# P00160_5_28_P.net
KiCad netlist of a schematic drawn in Altium Designer
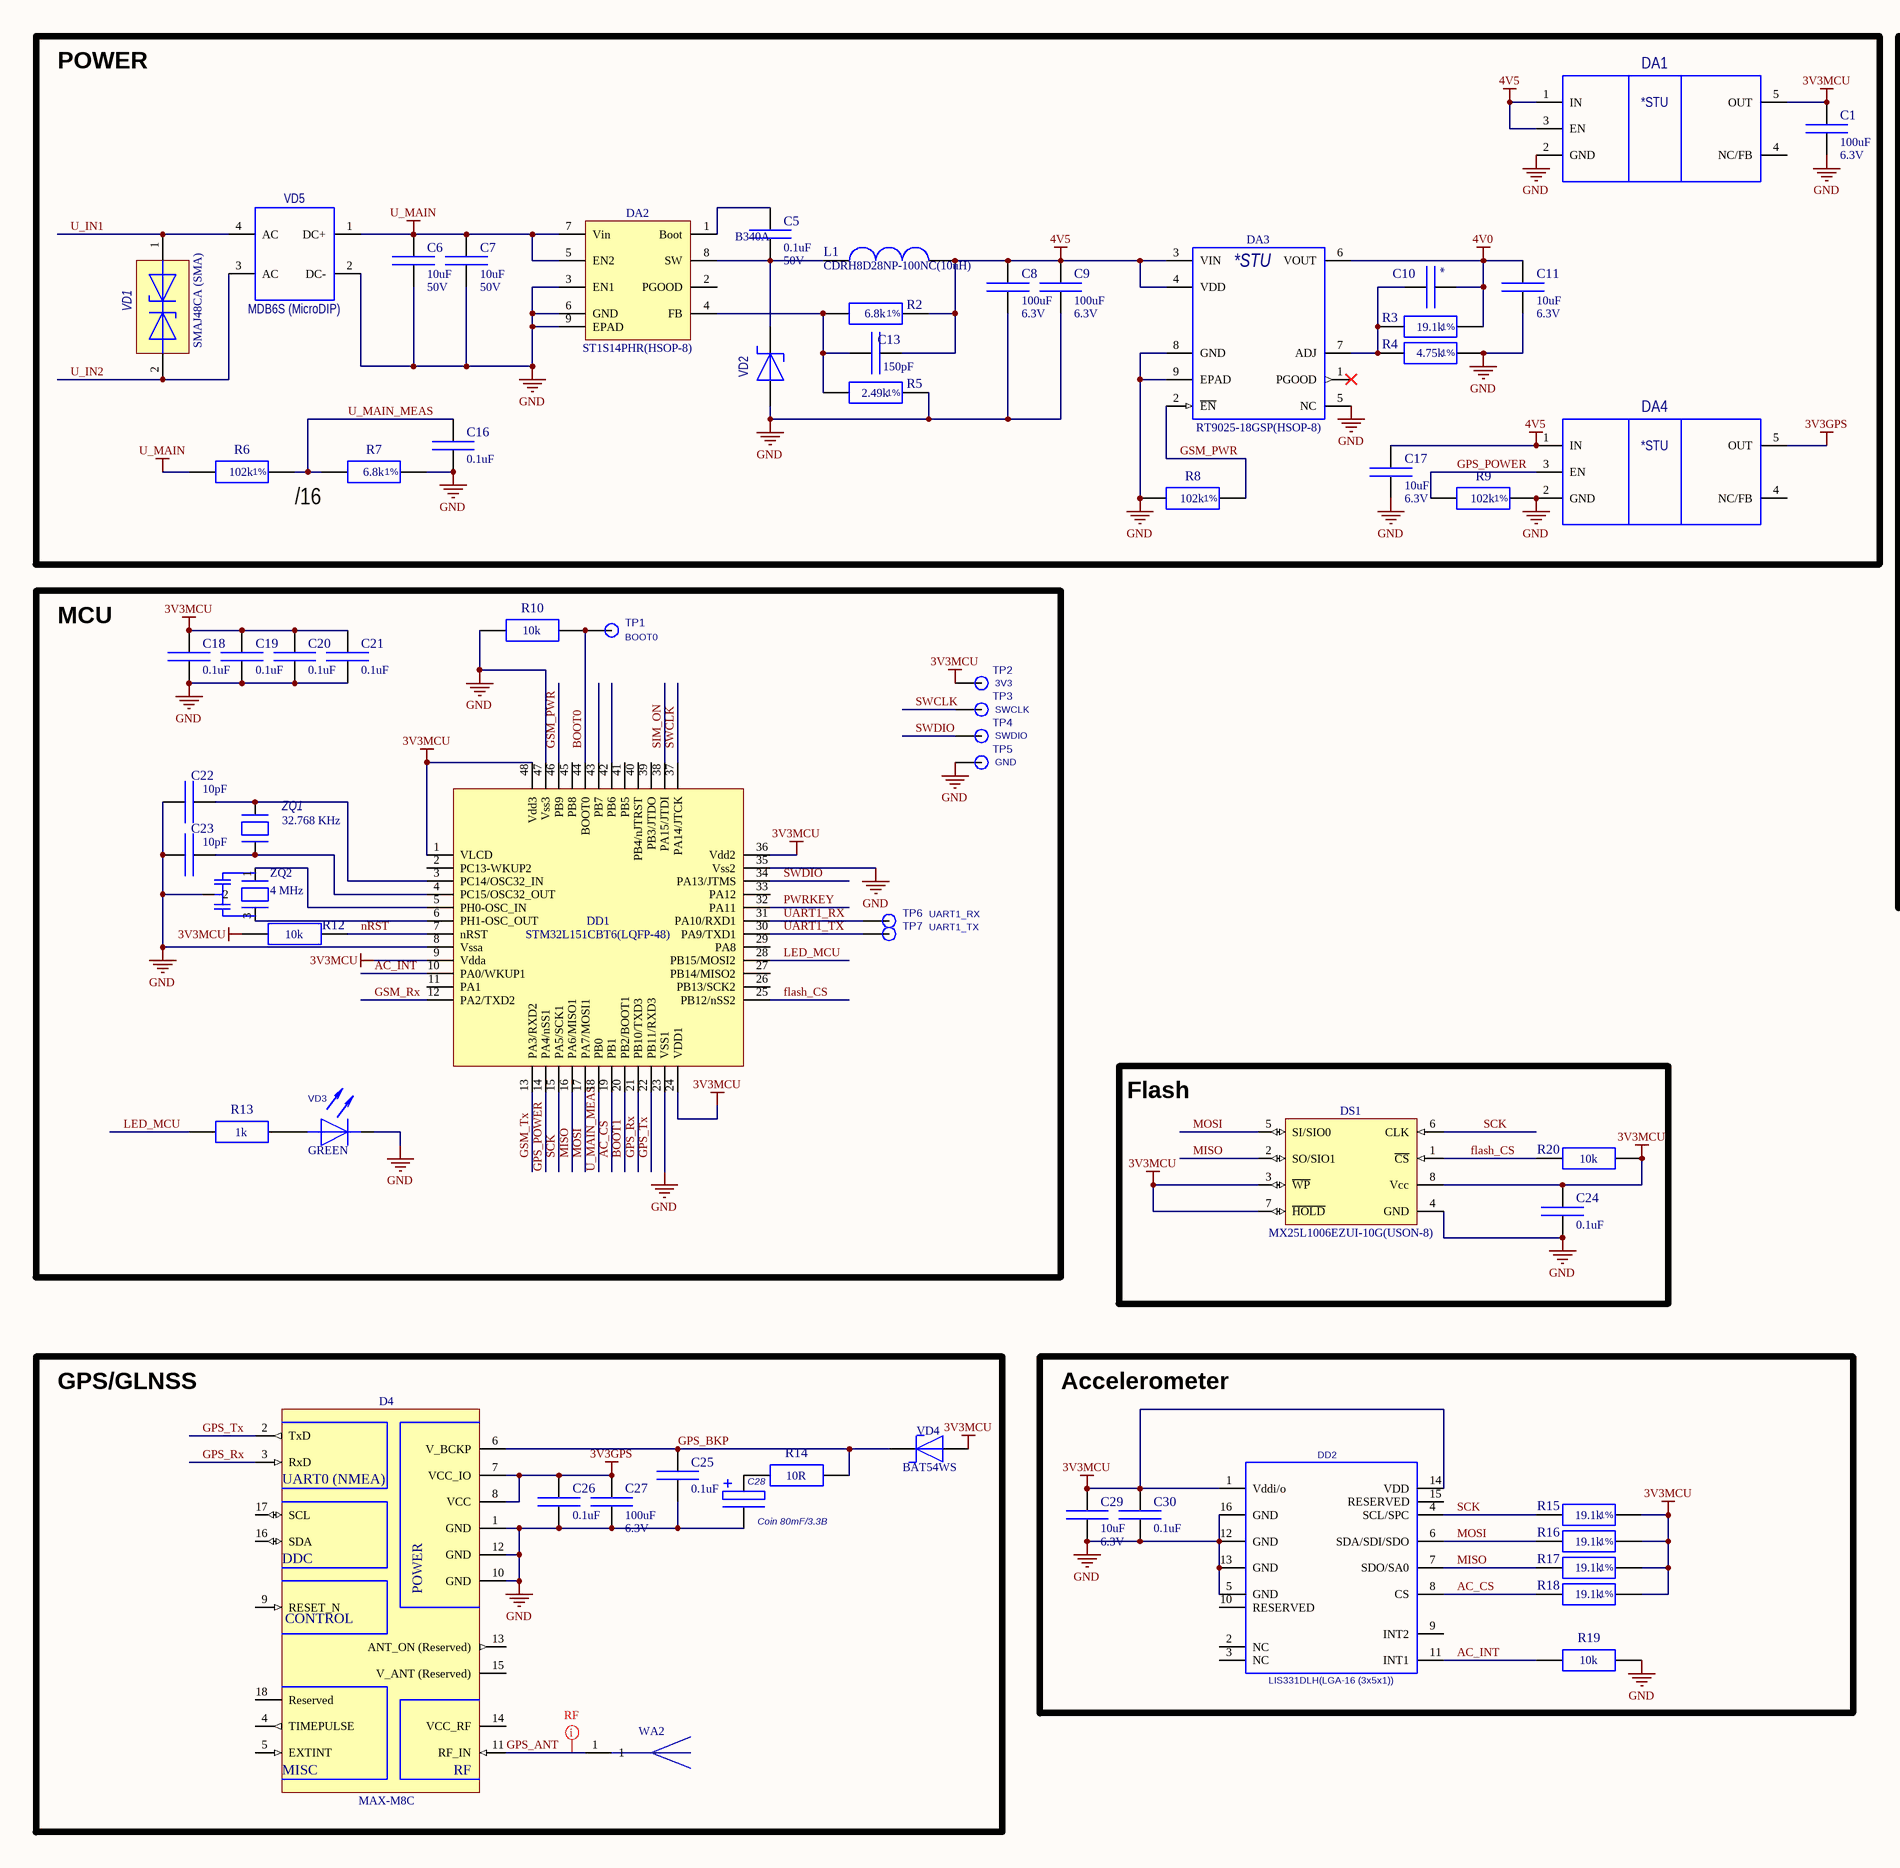
[diagram p0: P00160.5.28_P.SchDoc, left]
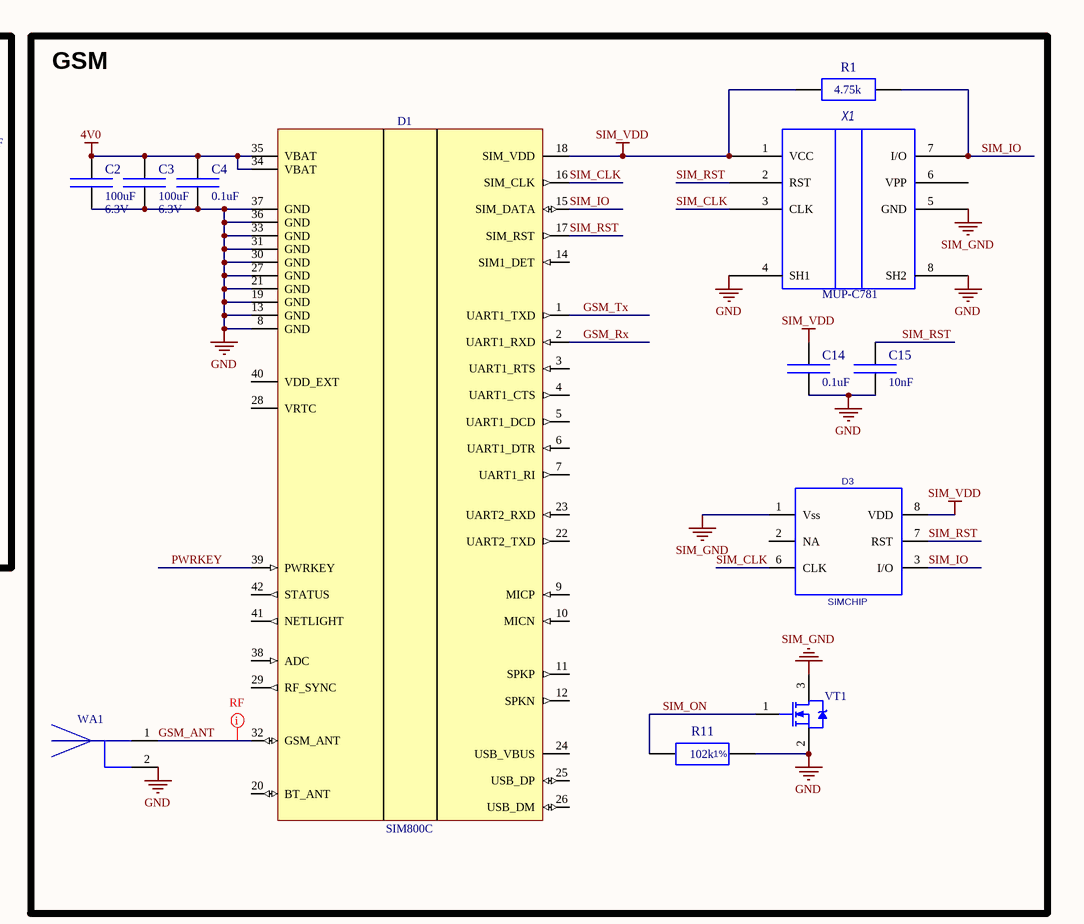
[diagram p1: P00160.5.28_P.SchDoc, right]

(export (version "E")
  (design (tool "Eeschema 10.0.6"))
  (components
    (comp (ref "C1")
      (value "100uF")
      (footprint "CAPC3216X135(1206)")
      (description "C1206")
      (fields (field (name "PARVOLTAGE") "6.3V") (field (name "Comment") "чип 1206 100uF/6.3V, "))
      (libsource (lib "pass_smd") (part "C1206"))
    )
    (comp (ref "C2")
      (value "100uF")
      (footprint "CAPC3216X135(1206)")
      (description "C1206")
      (fields (field (name "PARVOLTAGE") "6.3V") (field (name "Comment") "чип 1206 100uF/6.3V, "))
      (libsource (lib "pass_smd") (part "C1206"))
    )
    (comp (ref "C3")
      (value "100uF")
      (footprint "CAPC3216X135(1206)")
      (description "C1206")
      (fields (field (name "PARVOLTAGE") "6.3V") (field (name "Comment") "чип 1206 100uF/6.3V, "))
      (libsource (lib "pass_smd") (part "C1206"))
    )
    (comp (ref "C4")
      (value "0.1uF")
      (footprint "CAPC1005X50(0402)")
      (description "C0402")
      (fields (field (name "Comment") "чип 0402 0.1uF/10V, "))
      (libsource (lib "pass_smd") (part "C0402"))
    )
    (comp (ref "C5")
      (value "0.1uF")
      (footprint "CAPC1608X50(0603)")
      (description "C0603")
      (fields (field (name "PARVOLTAGE") "50V") (field (name "Comment") "чип 0603 0.1uF/50V, "))
      (libsource (lib "pass_smd") (part "C0603"))
    )
    (comp (ref "C6")
      (value "10uF")
      (footprint "CAPC3216X135(1206)")
      (description "C1206")
      (fields
        (field (name "CMPPARTNUM") "CL31A106KBHNNNE")
        (field (name "PARVOLTAGE") "50V")
        (field (name "Comment") "чип 1206 10uF/50V, ")
      )
      (libsource (lib "pass_smd") (part "C1206"))
    )
    (comp (ref "C7")
      (value "10uF")
      (footprint "CAPC3216X135(1206)")
      (description "C1206")
      (fields
        (field (name "CMPPARTNUM") "CL31A106KBHNNNE")
        (field (name "PARVOLTAGE") "50V")
        (field (name "Comment") "чип 1206 10uF/50V, ")
      )
      (libsource (lib "pass_smd") (part "C1206"))
    )
    (comp (ref "C8")
      (value "100uF")
      (footprint "CAPC3216X135(1206)")
      (description "C1206")
      (fields (field (name "PARVOLTAGE") "6.3V") (field (name "Comment") "чип 1206 100uF/6.3V, "))
      (libsource (lib "pass_smd") (part "C1206"))
    )
    (comp (ref "C9")
      (value "100uF")
      (footprint "CAPC3216X135(1206)")
      (description "C1206")
      (fields (field (name "PARVOLTAGE") "6.3V") (field (name "Comment") "чип 1206 100uF/6.3V, "))
      (libsource (lib "pass_smd") (part "C1206"))
    )
    (comp (ref "C10")
      (value "чип 0402 */,")
      (footprint "CAPC1005X50(0402)")
      (description "C0402")
      (fields (field (name "ALTIUM_VALUE") "*"))
      (libsource (lib "pass_smd") (part "C0402"))
    )
    (comp (ref "C11")
      (value "10uF")
      (footprint "CAPC1608X50(0603)")
      (description "C0603")
      (fields (field (name "PARVOLTAGE") "6.3V") (field (name "Comment") "чип 0603 10uF/6.3V, "))
      (libsource (lib "pass_smd") (part "C0603"))
    )
    (comp (ref "C13")
      (value "150pF")
      (footprint "CAPC1005X50(0402)")
      (description "C0402")
      (fields (field (name "Comment") "чип 0402 150pF/50V, "))
      (libsource (lib "pass_smd") (part "C0402"))
    )
    (comp (ref "C14")
      (value "0.1uF")
      (footprint "CAPC1005X50(0402)")
      (description "C0402")
      (fields (field (name "Comment") "чип 0402 0.1uF/10V, "))
      (libsource (lib "pass_smd") (part "C0402"))
    )
    (comp (ref "C15")
      (value "10nF")
      (footprint "CAPC1005X50(0402)")
      (description "C0402")
      (fields (field (name "Comment") "чип 0402 10nF/10V, "))
      (libsource (lib "pass_smd") (part "C0402"))
    )
    (comp (ref "C16")
      (value "0.1uF")
      (footprint "CAPC1005X50(0402)")
      (description "C0402")
      (fields (field (name "Comment") "чип 0402 0.1uF/10V, "))
      (libsource (lib "pass_smd") (part "C0402"))
    )
    (comp (ref "C17")
      (value "10uF")
      (footprint "CAPC1608X50(0603)")
      (description "C0603")
      (fields (field (name "PARVOLTAGE") "6.3V") (field (name "Comment") "чип 0603 10uF/6.3V, "))
      (libsource (lib "pass_smd") (part "C0603"))
    )
    (comp (ref "C18")
      (value "0.1uF")
      (footprint "CAPC1005X50(0402)")
      (description "C0402")
      (fields (field (name "Comment") "чип 0402 0.1uF/10V, "))
      (libsource (lib "pass_smd") (part "C0402"))
    )
    (comp (ref "C19")
      (value "0.1uF")
      (footprint "CAPC1005X50(0402)")
      (description "C0402")
      (fields (field (name "Comment") "чип 0402 0.1uF/10V, "))
      (libsource (lib "pass_smd") (part "C0402"))
    )
    (comp (ref "C20")
      (value "0.1uF")
      (footprint "CAPC1005X50(0402)")
      (description "C0402")
      (fields (field (name "Comment") "чип 0402 0.1uF/10V, "))
      (libsource (lib "pass_smd") (part "C0402"))
    )
    (comp (ref "C21")
      (value "0.1uF")
      (footprint "CAPC1005X50(0402)")
      (description "C0402")
      (fields (field (name "Comment") "чип 0402 0.1uF/10V, "))
      (libsource (lib "pass_smd") (part "C0402"))
    )
    (comp (ref "C22")
      (value "10pF")
      (footprint "CAPC1005X50(0402)")
      (description "C0402")
      (fields (field (name "Comment") "чип 0402 10pF/10V, "))
      (libsource (lib "pass_smd") (part "C0402"))
    )
    (comp (ref "C23")
      (value "10pF")
      (footprint "CAPC1005X50(0402)")
      (description "C0402")
      (fields (field (name "Comment") "чип 0402 10pF/10V, "))
      (libsource (lib "pass_smd") (part "C0402"))
    )
    (comp (ref "C24")
      (value "0.1uF")
      (footprint "CAPC1005X50(0402)")
      (description "C0402")
      (fields (field (name "Comment") "чип 0402 0.1uF/10V, "))
      (libsource (lib "pass_smd") (part "C0402"))
    )
    (comp (ref "C25")
      (value "0.1uF")
      (footprint "CAPC1005X50(0402)")
      (description "C0402")
      (fields (field (name "Comment") "чип 0402 0.1uF/10V, "))
      (libsource (lib "pass_smd") (part "C0402"))
    )
    (comp (ref "C26")
      (value "0.1uF")
      (footprint "CAPC1005X50(0402)")
      (description "C0402")
      (fields (field (name "Comment") "чип 0402 0.1uF/10V, "))
      (libsource (lib "pass_smd") (part "C0402"))
    )
    (comp (ref "C27")
      (value "100uF")
      (footprint "CAPC3216X135(1206)")
      (description "C1206")
      (fields (field (name "PARVOLTAGE") "6.3V") (field (name "Comment") "чип 1206 100uF/6.3V, "))
      (libsource (lib "pass_smd") (part "C1206"))
    )
    (comp (ref "C28")
      (value "Coin 80mF/3.3В")
      (footprint "XH414HG-IV01E")
      (description "ELECTRIC DOUBLE LAYER CAPACITORS")
      (fields (field (name "CMPPARTNUM") "XH414HG-IV01E"))
      (libsource (lib "MyLib") (part "XH414HG-IV01E"))
    )
    (comp (ref "C29")
      (value "10uF")
      (footprint "CAPC1608X50(0603)")
      (description "C0603")
      (fields (field (name "PARVOLTAGE") "6.3V") (field (name "Comment") "чип 0603 10uF/6.3V, "))
      (libsource (lib "pass_smd") (part "C0603"))
    )
    (comp (ref "C30")
      (value "0.1uF")
      (footprint "CAPC1005X50(0402)")
      (description "C0402")
      (fields (field (name "Comment") "чип 0402 0.1uF/10V, "))
      (libsource (lib "pass_smd") (part "C0402"))
    )
    (comp (ref "D1")
      (value "SIM800C")
      (footprint "SIMCOM800C")
      (libsource (lib "gsm_modules") (part "SIM800C"))
    )
    (comp (ref "D3")
      (value "SIMCHIP")
      (footprint "VQFN127P600-8N")
      (fields (field (name "CMPPARTNUM") "MFF2 SIM"))
      (libsource (lib "Misc") (part "SIMCHIP"))
    )
    (comp (ref "D4") (value "MAX-M8C") (footprint "MAX-7") (libsource (lib "gps_modules") (part "MAX-7")))
    (comp (ref "DA1")
      (value "TPS76333DBV(SOT23-5)")
      (footprint "SOT95P285X130-5N(SOT23-5)")
      (description "TPS76333DBV")
      (libsource (lib "TI") (part "TPS76333DBV"))
    )
    (comp (ref "DA2")
      (value "ST1S14PHR(HSOP-8)")
      (footprint "HSOP127P-8N")
      (fields (field (name "CMPPARTNUM") "ST1S14PHR"))
      (libsource (lib "ST") (part "ST1S14"))
    )
    (comp (ref "DA3")
      (value "RT9025-18GSP(HSOP-8)")
      (footprint "HSOP127P-8N")
      (description "2A, Ultra Low Dropout LDO")
      (fields (field (name "CMPPARTNUM") "RT9025-18GSP"))
      (libsource (lib "Richtek") (part "RT9025"))
    )
    (comp (ref "DA4")
      (value "TPS76333DBV(SOT23-5)")
      (footprint "SOT95P285X130-5N(SOT23-5)")
      (description "TPS76333DBV")
      (libsource (lib "TI") (part "TPS76333DBV"))
    )
    (comp (ref "DD1")
      (value "STM32L151CBT6(LQFP-48)")
      (footprint "TSQFP50P900X900X160-48N")
      (description "STM32L151CxU6")
      (fields (field (name "CMPPARTNUM") "STM32L151CBT6"))
      (libsource (lib "ST") (part "STM32L151CxU6"))
    )
    (comp (ref "DD2")
      (value "LIS331DLH(LGA-16 (3x5x1))")
      (footprint "LGA16S50P3X5_300X300X100")
      (description "MEMS digital output motion sensor  ultra low-power high performance 3-axes “nano” accelerometer")
      (fields (field (name "CMPPARTNUM") "LIS331DLH"))
      (libsource (lib "ST") (part "LIS331DLH"))
    )
    (comp (ref "DS1")
      (value "MX25L1006EZUI-10G(USON-8)")
      (footprint "SON50P300X60_HS-9N")
      (description "1M-BIT [x 1/x 2] CMOS SERIAL FLASH")
      (fields (field (name "CMPPARTNUM") "MX25L1006EZUI-10G"))
      (libsource (lib "ROMs") (part "MX25L1006E"))
    )
    (comp (ref "L1")
      (value "CDRH8D28NP-100NC(10uH)")
      (footprint "CDRH8D28NP")
      (description "CDRH8D28NP")
      (fields (field (name "CMPPARTNUM") "CDRH8D28NP-100NC"))
      (libsource (lib "pass_smd") (part "CDRH8D28NP"))
    )
    (comp (ref "R1")
      (value "4.75k")
      (footprint "RESC1005X35(0402)")
      (description "R0402")
      (fields (field (name "TOLERANCE") "1%") (field (name "Comment") "чип 0402 4.75k 1%"))
      (libsource (lib "pass_smd") (part "R0402"))
    )
    (comp (ref "R2")
      (value "6.8k")
      (footprint "RESC1005X35(0402)")
      (description "R0402")
      (fields (field (name "TOLERANCE") "1%") (field (name "Comment") "чип 0402 6.8k 1%"))
      (libsource (lib "pass_smd") (part "R0402"))
    )
    (comp (ref "R3")
      (value "19.1k")
      (footprint "RESC1005X35(0402)")
      (description "R0402")
      (fields (field (name "TOLERANCE") "1%") (field (name "Comment") "чип 0402 19.1k 1%"))
      (libsource (lib "pass_smd") (part "R0402"))
    )
    (comp (ref "R4")
      (value "4.75k")
      (footprint "RESC1005X35(0402)")
      (description "R0402")
      (fields (field (name "TOLERANCE") "1%") (field (name "Comment") "чип 0402 4.75k 1%"))
      (libsource (lib "pass_smd") (part "R0402"))
    )
    (comp (ref "R5")
      (value "2.49k")
      (footprint "RESC1005X35(0402)")
      (description "R0402")
      (fields (field (name "TOLERANCE") "1%") (field (name "Comment") "чип 0402 2.49k 1%"))
      (libsource (lib "pass_smd") (part "R0402"))
    )
    (comp (ref "R6")
      (value "102k")
      (footprint "RESC1005X35(0402)")
      (description "R0402")
      (fields (field (name "TOLERANCE") "1%") (field (name "Comment") "чип 0402 102k 1%"))
      (libsource (lib "pass_smd") (part "R0402"))
    )
    (comp (ref "R7")
      (value "6.8k")
      (footprint "RESC1005X35(0402)")
      (description "R0402")
      (fields (field (name "TOLERANCE") "1%") (field (name "Comment") "чип 0402 6.8k 1%"))
      (libsource (lib "pass_smd") (part "R0402"))
    )
    (comp (ref "R8")
      (value "102k")
      (footprint "RESC1005X35(0402)")
      (description "R0402")
      (fields (field (name "TOLERANCE") "1%") (field (name "Comment") "чип 0402 102k 1%"))
      (libsource (lib "pass_smd") (part "R0402"))
    )
    (comp (ref "R9")
      (value "102k")
      (footprint "RESC1005X35(0402)")
      (description "R0402")
      (fields (field (name "TOLERANCE") "1%") (field (name "Comment") "чип 0402 102k 1%"))
      (libsource (lib "pass_smd") (part "R0402"))
    )
    (comp (ref "R10")
      (value "10k")
      (footprint "RESC1005X35(0402)")
      (description "R0402")
      (fields (field (name "TOLERANCE") "5%") (field (name "Comment") "чип 0402 10k 5%"))
      (libsource (lib "pass_smd") (part "R0402"))
    )
    (comp (ref "R11")
      (value "102k")
      (footprint "RESC1005X35(0402)")
      (description "R0402")
      (fields (field (name "TOLERANCE") "1%") (field (name "Comment") "чип 0402 102k 1%"))
      (libsource (lib "pass_smd") (part "R0402"))
    )
    (comp (ref "R12")
      (value "10k")
      (footprint "RESC1005X35(0402)")
      (description "R0402")
      (fields (field (name "TOLERANCE") "5%") (field (name "Comment") "чип 0402 10k 5%"))
      (libsource (lib "pass_smd") (part "R0402"))
    )
    (comp (ref "R13")
      (value "1k")
      (footprint "RESC1005X35(0402)")
      (description "R0402")
      (fields (field (name "TOLERANCE") "5%") (field (name "Comment") "чип 0402 1k 5%"))
      (libsource (lib "pass_smd") (part "R0402"))
    )
    (comp (ref "R14")
      (value "10R")
      (footprint "RESC1005X35(0402)")
      (description "R0402")
      (fields (field (name "TOLERANCE") "5%") (field (name "Comment") "чип 0402 10R 5%"))
      (libsource (lib "pass_smd") (part "R0402"))
    )
    (comp (ref "R15")
      (value "19.1k")
      (footprint "RESC1005X35(0402)")
      (description "R0402")
      (fields (field (name "TOLERANCE") "1%") (field (name "Comment") "чип 0402 19.1k 1%"))
      (libsource (lib "pass_smd") (part "R0402"))
    )
    (comp (ref "R16")
      (value "19.1k")
      (footprint "RESC1005X35(0402)")
      (description "R0402")
      (fields (field (name "TOLERANCE") "1%") (field (name "Comment") "чип 0402 19.1k 1%"))
      (libsource (lib "pass_smd") (part "R0402"))
    )
    (comp (ref "R17")
      (value "19.1k")
      (footprint "RESC1005X35(0402)")
      (description "R0402")
      (fields (field (name "TOLERANCE") "1%") (field (name "Comment") "чип 0402 19.1k 1%"))
      (libsource (lib "pass_smd") (part "R0402"))
    )
    (comp (ref "R18")
      (value "19.1k")
      (footprint "RESC1005X35(0402)")
      (description "R0402")
      (fields (field (name "TOLERANCE") "1%") (field (name "Comment") "чип 0402 19.1k 1%"))
      (libsource (lib "pass_smd") (part "R0402"))
    )
    (comp (ref "R19")
      (value "10k")
      (footprint "RESC1005X35(0402)")
      (description "R0402")
      (fields (field (name "TOLERANCE") "5%") (field (name "Comment") "чип 0402 10k 5%"))
      (libsource (lib "pass_smd") (part "R0402"))
    )
    (comp (ref "R20")
      (value "10k")
      (footprint "RESC1005X35(0402)")
      (description "R0402")
      (fields (field (name "TOLERANCE") "5%") (field (name "Comment") "чип 0402 10k 5%"))
      (libsource (lib "pass_smd") (part "R0402"))
    )
    (comp (ref "TP1")
      (value "BOOT0")
      (footprint "TEST_POINT")
      (description "TEST_POINT")
      (libsource (lib "connectors") (part "TEST_POINT"))
    )
    (comp (ref "TP2")
      (value "3V3")
      (footprint "TEST_POINT")
      (description "TEST_POINT")
      (libsource (lib "connectors") (part "TEST_POINT"))
    )
    (comp (ref "TP3")
      (value "SWCLK")
      (footprint "TEST_POINT")
      (description "TEST_POINT")
      (libsource (lib "connectors") (part "TEST_POINT"))
    )
    (comp (ref "TP4")
      (value "SWDIO")
      (footprint "TEST_POINT")
      (description "TEST_POINT")
      (libsource (lib "connectors") (part "TEST_POINT"))
    )
    (comp (ref "TP5")
      (value "GND")
      (footprint "TEST_POINT")
      (description "TEST_POINT")
      (libsource (lib "connectors") (part "TEST_POINT"))
    )
    (comp (ref "TP6")
      (value "UART1_RX")
      (footprint "TEST_POINT")
      (description "TEST_POINT")
      (libsource (lib "connectors") (part "TEST_POINT"))
    )
    (comp (ref "TP7")
      (value "UART1_TX")
      (footprint "TEST_POINT")
      (description "TEST_POINT")
      (libsource (lib "connectors") (part "TEST_POINT"))
    )
    (comp (ref "VD1")
      (value "SMAJ48CA (SMA)")
      (footprint "DIOM5226X267N (SMA) B")
      (description "Zener (TVS) Diode in SMA package Bidirectional")
      (fields (field (name "CMPPARTNUM") "SMAJ48CA"))
      (libsource (lib "diodes") (part "SMA Zener (Bidir)"))
    )
    (comp (ref "VD2")
      (value "B340A (SMA)")
      (footprint "DIOM5226X267N (SMA)")
      (description "Schottky diode in SMA Case")
      (fields (field (name "CMPPARTNUM") "B340A"))
      (libsource (lib "diodes") (part "SMA SCHOTTKY"))
    )
    (comp (ref "VD3")
      (value "APHHS1005SURCK (чип 0402)")
      (footprint "LED1005X50N(0402)_GREEN")
      (description "LED 0402")
      (fields (field (name "CMPPARTNUM") "APHHS1005SURCK") (field (name "PARCOLOR") "GREEN"))
      (libsource (lib "diodes") (part "LED 0402"))
    )
    (comp (ref "VD4")
      (value "BAT54WS (SOD323)")
      (footprint "SOD2514X110N(SOD323)")
      (description "BAT54WS")
      (fields (field (name "CMPPARTNUM") "BAT54WS"))
      (libsource (lib "diodes") (part "SOD323 SCHOTTKY"))
    )
    (comp (ref "VD5")
      (value "MDB6S (MicroDIP)")
      (footprint "Micro-DIP")
      (description "B1S-B10S 0.5 surface mount glass passivated bridge rectifier")
      (fields (field (name "CMPPARTNUM") "MDB6S"))
      (libsource (lib "diodes") (part "MDB6S"))
    )
    (comp (ref "VT1")
      (value "IRLML0030TRPBF (SOT-23)")
      (footprint "SOT95P230-3N (SOT-23) num")
      (description "HEXFET Power MOSFET")
      (fields (field (name "CMPPARTNUM") "IRLML0030TRPBF"))
      (libsource (lib "transistors") (part "IRLML0030"))
    )
    (comp (ref "WA1")
      (value "~")
      (footprint "PCB_ANT")
      (description "CLIP_ANT")
      (libsource (lib "MyLib") (part "ANT_PCB_CLIP"))
    )
    (comp (ref "WA2")
      (value "UDA182-180-1575-C-GPS-GLONASS-PCB")
      (footprint "UDA182")
      (description "A25, UDA25, A18")
      (libsource (lib "Misc") (part "GPS antenna Pass"))
    )
    (comp (ref "X1")
      (value "MUP Connectors MUP-C781")
      (footprint "MUP-C781")
      (description "Sim Holder MUP-C781")
      (fields (field (name "CMPPARTNUM") "MUP-C781"))
      (libsource (lib "connectors") (part "SIM MUP-C781"))
    )
    (comp (ref "ZQ1")
      (value "32.768 KHz")
      (footprint "XTAL320X150X90-2N(DST)")
      (description "DST310S")
      (fields (field (name "Comment") "DST310S(32.768 KHz)"))
      (libsource (lib "xtal") (part "XTAL, SMD, 3.2mm x 1.5mm, 2 pads"))
    )
    (comp (ref "ZQ2")
      (value "4 MHz")
      (footprint "XTAL450X200X120 (CSTCR)")
      (description "CSTCR_G15C Ceramic Resonators")
      (fields (field (name "CMPPARTNUM") "CSTCR4M00G15C99-R0") (field (name "TOLERANCE") "±0.5%"))
      (libsource (lib "xtal") (part "XTAL, SMD, 4.5mm x 2mm, 3 pads"))
    )
  )
  (nets
    (net (code "1") (name "/AC_CS") (class "Default")
      (node (ref "DD1") (pin "19") (pinfunction "PB1_19") (pintype "passive"))
      (node (ref "DD2") (pin "8") (pinfunction "CS_8") (pintype "passive"))
      (node (ref "R18") (pin "1") (pinfunction "1_1") (pintype "passive"))
    )
    (net (code "2") (name "/AC_INT") (class "Default")
      (node (ref "DD1") (pin "10") (pinfunction "PA0/WKUP1_10") (pintype "passive"))
      (node (ref "DD2") (pin "11") (pinfunction "INT1_11") (pintype "passive"))
      (node (ref "R19") (pin "1") (pinfunction "1_1") (pintype "passive"))
    )
    (net (code "3") (name "/BOOT0") (class "Default")
      (node (ref "DD1") (pin "44") (pinfunction "BOOT0_44") (pintype "passive"))
      (node (ref "R10") (pin "2") (pinfunction "2_2") (pintype "passive"))
      (node (ref "TP1") (pin "1") (pintype "passive"))
    )
    (net (code "4") (name "/BOOT1") (class "Default")
      (node (ref "DD1") (pin "20") (pinfunction "PB2/BOOT1_20") (pintype "passive"))
    )
    (net (code "5") (name "/GPS_ANT") (class "Default")
      (node (ref "D4") (pin "11") (pinfunction "RF_IN_11") (pintype "input"))
      (node (ref "WA2") (pin "1") (pinfunction "1_1") (pintype "passive"))
    )
    (net (code "6") (name "/GPS_BKP") (class "Default")
      (node (ref "C25") (pin "2") (pinfunction "P2_2") (pintype "passive"))
      (node (ref "D4") (pin "6") (pinfunction "V_BCKP_6") (pintype "power_in"))
      (node (ref "R14") (pin "2") (pinfunction "2_2") (pintype "passive"))
      (node (ref "VD4") (pin "C") (pinfunction "C_C") (pintype "passive"))
    )
    (net (code "7") (name "/GPS_POWER") (class "Default")
      (node (ref "DA4") (pin "3") (pinfunction "EN_3") (pintype "passive"))
      (node (ref "DD1") (pin "14") (pinfunction "PA4/nSS1_14") (pintype "passive"))
      (node (ref "R9") (pin "1") (pinfunction "1_1") (pintype "passive"))
    )
    (net (code "8") (name "/GPS_Rx") (class "Default")
      (node (ref "D4") (pin "3") (pinfunction "RxD_3") (pintype "input"))
      (node (ref "DD1") (pin "21") (pinfunction "PB10/TXD3_21") (pintype "passive"))
    )
    (net (code "9") (name "/GPS_Tx") (class "Default")
      (node (ref "D4") (pin "2") (pinfunction "TxD_2") (pintype "output"))
      (node (ref "DD1") (pin "22") (pinfunction "PB11/RXD3_22") (pintype "passive"))
    )
    (net (code "10") (name "/GSM_ANT") (class "Default")
      (node (ref "D1") (pin "32") (pinfunction "GSM_ANT_32") (pintype "bidirectional"))
      (node (ref "WA1") (pin "1") (pinfunction "1_1") (pintype "passive"))
    )
    (net (code "11") (name "/GSM_PWR") (class "Default")
      (node (ref "DA3") (pin "2") (pinfunction "~{EN}_2") (pintype "input"))
      (node (ref "DD1") (pin "46") (pinfunction "PB9_46") (pintype "passive"))
      (node (ref "R8") (pin "2") (pinfunction "2_2") (pintype "passive"))
    )
    (net (code "12") (name "/GSM_Rx") (class "Default")
      (node (ref "D1") (pin "2") (pinfunction "UART1_RXD_2") (pintype "input"))
      (node (ref "DD1") (pin "12") (pinfunction "PA2/TXD2_12") (pintype "passive"))
    )
    (net (code "13") (name "/GSM_Tx") (class "Default")
      (node (ref "D1") (pin "1") (pinfunction "UART1_TXD_1") (pintype "output"))
      (node (ref "DD1") (pin "13") (pinfunction "PA3/RXD2_13") (pintype "passive"))
    )
    (net (code "14") (name "/LED_MCU") (class "Default")
      (node (ref "DD1") (pin "28") (pinfunction "PB15/MOSI2_28") (pintype "passive"))
      (node (ref "R13") (pin "1") (pinfunction "1_1") (pintype "passive"))
    )
    (net (code "15") (name "/MISO") (class "Default")
      (node (ref "DD1") (pin "16") (pinfunction "PA6/MISO1_16") (pintype "passive"))
      (node (ref "DD2") (pin "7") (pinfunction "SDO/SA0_7") (pintype "passive"))
      (node (ref "DS1") (pin "2") (pinfunction "SO/SIO1_2") (pintype "bidirectional"))
      (node (ref "R17") (pin "1") (pinfunction "1_1") (pintype "passive"))
    )
    (net (code "16") (name "/MOSI") (class "Default")
      (node (ref "DD1") (pin "17") (pinfunction "PA7/MOSI1_17") (pintype "passive"))
      (node (ref "DD2") (pin "6") (pinfunction "SDA/SDI/SDO_6") (pintype "passive"))
      (node (ref "DS1") (pin "5") (pinfunction "SI/SIO0_5") (pintype "bidirectional"))
      (node (ref "R16") (pin "1") (pinfunction "1_1") (pintype "passive"))
    )
    (net (code "17") (name "/PWRKEY") (class "Default")
      (node (ref "D1") (pin "39") (pinfunction "PWRKEY_39") (pintype "input"))
      (node (ref "DD1") (pin "32") (pinfunction "PA11_32") (pintype "passive"))
    )
    (net (code "18") (name "/SCK") (class "Default")
      (node (ref "DD1") (pin "15") (pinfunction "PA5/SCK1_15") (pintype "passive"))
      (node (ref "DD2") (pin "4") (pinfunction "SCL/SPC_4") (pintype "passive"))
      (node (ref "DS1") (pin "6") (pinfunction "CLK_6") (pintype "input"))
      (node (ref "R15") (pin "1") (pinfunction "1_1") (pintype "passive"))
    )
    (net (code "19") (name "/SIM_CLK") (class "Default")
      (node (ref "D1") (pin "16") (pinfunction "SIM_CLK_16") (pintype "output"))
      (node (ref "D3") (pin "6") (pinfunction "CLK_6") (pintype "passive"))
      (node (ref "X1") (pin "3") (pinfunction "CLK_3") (pintype "passive"))
    )
    (net (code "20") (name "/SIM_IO") (class "Default")
      (node (ref "D1") (pin "15") (pinfunction "SIM_DATA_15") (pintype "bidirectional"))
      (node (ref "D3") (pin "3") (pinfunction "I/O_3") (pintype "passive"))
      (node (ref "R1") (pin "2") (pinfunction "2_2") (pintype "passive"))
      (node (ref "X1") (pin "7") (pinfunction "I/O_7") (pintype "passive"))
    )
    (net (code "21") (name "/SIM_ON") (class "Default")
      (node (ref "DD1") (pin "38") (pinfunction "PA15/JTDI_38") (pintype "passive"))
      (node (ref "R11") (pin "1") (pinfunction "1_1") (pintype "passive"))
      (node (ref "VT1") (pin "1") (pinfunction "G_1") (pintype "passive"))
    )
    (net (code "22") (name "/SIM_RST") (class "Default")
      (node (ref "C15") (pin "2") (pinfunction "P2_2") (pintype "passive"))
      (node (ref "D1") (pin "17") (pinfunction "SIM_RST_17") (pintype "output"))
      (node (ref "D3") (pin "7") (pinfunction "RST_7") (pintype "passive"))
      (node (ref "X1") (pin "2") (pinfunction "RST_2") (pintype "passive"))
    )
    (net (code "23") (name "/SWCLK") (class "Default")
      (node (ref "DD1") (pin "37") (pinfunction "PA14/JTCK_37") (pintype "passive"))
      (node (ref "TP3") (pin "1") (pintype "passive"))
    )
    (net (code "24") (name "/SWDIO") (class "Default")
      (node (ref "DD1") (pin "34") (pinfunction "PA13/JTMS_34") (pintype "passive"))
      (node (ref "TP4") (pin "1") (pintype "passive"))
    )
    (net (code "25") (name "/UART1_RX") (class "Default")
      (node (ref "DD1") (pin "31") (pinfunction "PA10/RXD1_31") (pintype "passive"))
      (node (ref "TP6") (pin "1") (pintype "passive"))
    )
    (net (code "26") (name "/UART1_TX") (class "Default")
      (node (ref "DD1") (pin "30") (pinfunction "PA9/TXD1_30") (pintype "passive"))
      (node (ref "TP7") (pin "1") (pintype "passive"))
    )
    (net (code "27") (name "/U_IN1") (class "Default")
      (node (ref "VD1") (pin "1") (pinfunction "1_1") (pintype "passive"))
      (node (ref "VD5") (pin "4") (pinfunction "AC_4") (pintype "passive"))
    )
    (net (code "28") (name "/U_IN2") (class "Default")
      (node (ref "VD1") (pin "2") (pinfunction "2_2") (pintype "passive"))
      (node (ref "VD5") (pin "3") (pinfunction "AC_3") (pintype "passive"))
    )
    (net (code "29") (name "/U_MAIN_MEAS") (class "Default")
      (node (ref "C16") (pin "2") (pinfunction "P2_2") (pintype "passive"))
      (node (ref "DD1") (pin "18") (pinfunction "PB0_18") (pintype "passive"))
      (node (ref "R6") (pin "2") (pinfunction "2_2") (pintype "passive"))
      (node (ref "R7") (pin "1") (pinfunction "1_1") (pintype "passive"))
    )
    (net (code "30") (name "/flash_CS") (class "Default")
      (node (ref "DD1") (pin "25") (pinfunction "PB12/nSS2_25") (pintype "passive"))
      (node (ref "DS1") (pin "1") (pinfunction "CS_1") (pintype "input"))
      (node (ref "R20") (pin "1") (pinfunction "1_1") (pintype "passive"))
    )
    (net (code "31") (name "/nRST") (class "Default")
      (node (ref "DD1") (pin "7") (pinfunction "nRST_7") (pintype "passive"))
      (node (ref "R12") (pin "2") (pinfunction "2_2") (pintype "passive"))
    )
    (net (code "32") (name "3V3GPS") (class "Default")
      (node (ref "C26") (pin "2") (pinfunction "P2_2") (pintype "passive"))
      (node (ref "C27") (pin "1") (pinfunction "1_1") (pintype "passive"))
      (node (ref "D4") (pin "7") (pinfunction "VCC_IO_7") (pintype "power_in"))
      (node (ref "D4") (pin "8") (pinfunction "VCC_8") (pintype "power_in"))
      (node (ref "DA4") (pin "5") (pinfunction "OUT_5") (pintype "passive"))
    )
    (net (code "33") (name "3V3MCU") (class "Default")
      (node (ref "C1") (pin "1") (pinfunction "1_1") (pintype "passive"))
      (node (ref "C18") (pin "2") (pinfunction "P2_2") (pintype "passive"))
      (node (ref "C19") (pin "2") (pinfunction "P2_2") (pintype "passive"))
      (node (ref "C20") (pin "2") (pinfunction "P2_2") (pintype "passive"))
      (node (ref "C21") (pin "2") (pinfunction "P2_2") (pintype "passive"))
      (node (ref "C24") (pin "2") (pinfunction "P2_2") (pintype "passive"))
      (node (ref "C29") (pin "2") (pinfunction "2_2") (pintype "passive"))
      (node (ref "C30") (pin "2") (pinfunction "P2_2") (pintype "passive"))
      (node (ref "DA1") (pin "5") (pinfunction "OUT_5") (pintype "passive"))
      (node (ref "DD1") (pin "1") (pinfunction "VLCD_1") (pintype "passive"))
      (node (ref "DD1") (pin "24") (pinfunction "VDD1_24") (pintype "passive"))
      (node (ref "DD1") (pin "36") (pinfunction "Vdd2_36") (pintype "passive"))
      (node (ref "DD1") (pin "48") (pinfunction "Vdd3_48") (pintype "passive"))
      (node (ref "DD1") (pin "9") (pinfunction "Vdda_9") (pintype "passive"))
      (node (ref "DD2") (pin "1") (pinfunction "Vddi/o_1") (pintype "passive"))
      (node (ref "DD2") (pin "14") (pinfunction "VDD_14") (pintype "passive"))
      (node (ref "DS1") (pin "3") (pinfunction "~{WP}_3") (pintype "bidirectional"))
      (node (ref "DS1") (pin "7") (pinfunction "~{HOLD}_7") (pintype "bidirectional"))
      (node (ref "DS1") (pin "8") (pinfunction "Vcc_8") (pintype "passive"))
      (node (ref "R12") (pin "1") (pinfunction "1_1") (pintype "passive"))
      (node (ref "R15") (pin "2") (pinfunction "2_2") (pintype "passive"))
      (node (ref "R16") (pin "2") (pinfunction "2_2") (pintype "passive"))
      (node (ref "R17") (pin "2") (pinfunction "2_2") (pintype "passive"))
      (node (ref "R18") (pin "2") (pinfunction "2_2") (pintype "passive"))
      (node (ref "R20") (pin "2") (pinfunction "2_2") (pintype "passive"))
      (node (ref "TP2") (pin "1") (pintype "passive"))
      (node (ref "VD4") (pin "A") (pinfunction "A_A") (pintype "passive"))
    )
    (net (code "34") (name "4V0") (class "Default")
      (node (ref "C10") (pin "1") (pinfunction "P1_1") (pintype "passive"))
      (node (ref "C11") (pin "2") (pinfunction "2_2") (pintype "passive"))
      (node (ref "C2") (pin "1") (pinfunction "1_1") (pintype "passive"))
      (node (ref "C3") (pin "1") (pinfunction "1_1") (pintype "passive"))
      (node (ref "C4") (pin "2") (pinfunction "P2_2") (pintype "passive"))
      (node (ref "D1") (pin "34") (pinfunction "VBAT_34") (pintype "power_in"))
      (node (ref "D1") (pin "35") (pinfunction "VBAT_35") (pintype "power_in"))
      (node (ref "DA3") (pin "6") (pinfunction "VOUT_6") (pintype "power_in"))
      (node (ref "R3") (pin "2") (pinfunction "2_2") (pintype "passive"))
    )
    (net (code "35") (name "4V5") (class "Default")
      (node (ref "C13") (pin "1") (pinfunction "P1_1") (pintype "passive"))
      (node (ref "C17") (pin "2") (pinfunction "2_2") (pintype "passive"))
      (node (ref "C8") (pin "1") (pinfunction "1_1") (pintype "passive"))
      (node (ref "C9") (pin "1") (pinfunction "1_1") (pintype "passive"))
      (node (ref "DA1") (pin "1") (pinfunction "IN_1") (pintype "passive"))
      (node (ref "DA1") (pin "3") (pinfunction "EN_3") (pintype "passive"))
      (node (ref "DA3") (pin "3") (pinfunction "VIN_3") (pintype "power_in"))
      (node (ref "DA3") (pin "4") (pinfunction "VDD_4") (pintype "power_in"))
      (node (ref "DA4") (pin "1") (pinfunction "IN_1") (pintype "passive"))
      (node (ref "L1") (pin "2") (pinfunction "2_2") (pintype "passive"))
      (node (ref "R2") (pin "2") (pinfunction "2_2") (pintype "passive"))
    )
    (net (code "36") (name "GND") (class "Default")
      (node (ref "C1") (pin "2") (pinfunction "2_2") (pintype "passive"))
      (node (ref "C11") (pin "1") (pinfunction "1_1") (pintype "passive"))
      (node (ref "C14") (pin "1") (pinfunction "P1_1") (pintype "passive"))
      (node (ref "C15") (pin "1") (pinfunction "P1_1") (pintype "passive"))
      (node (ref "C16") (pin "1") (pinfunction "P1_1") (pintype "passive"))
      (node (ref "C17") (pin "1") (pinfunction "1_1") (pintype "passive"))
      (node (ref "C18") (pin "1") (pinfunction "P1_1") (pintype "passive"))
      (node (ref "C19") (pin "1") (pinfunction "P1_1") (pintype "passive"))
      (node (ref "C2") (pin "2") (pinfunction "2_2") (pintype "passive"))
      (node (ref "C20") (pin "1") (pinfunction "P1_1") (pintype "passive"))
      (node (ref "C21") (pin "1") (pinfunction "P1_1") (pintype "passive"))
      (node (ref "C22") (pin "2") (pinfunction "P2_2") (pintype "passive"))
      (node (ref "C23") (pin "2") (pinfunction "P2_2") (pintype "passive"))
      (node (ref "C24") (pin "1") (pinfunction "P1_1") (pintype "passive"))
      (node (ref "C25") (pin "1") (pinfunction "P1_1") (pintype "passive"))
      (node (ref "C26") (pin "1") (pinfunction "P1_1") (pintype "passive"))
      (node (ref "C27") (pin "2") (pinfunction "2_2") (pintype "passive"))
      (node (ref "C28") (pin "2") (pinfunction "2_2") (pintype "passive"))
      (node (ref "C29") (pin "1") (pinfunction "1_1") (pintype "passive"))
      (node (ref "C3") (pin "2") (pinfunction "2_2") (pintype "passive"))
      (node (ref "C30") (pin "1") (pinfunction "P1_1") (pintype "passive"))
      (node (ref "C4") (pin "1") (pinfunction "P1_1") (pintype "passive"))
      (node (ref "C6") (pin "2") (pinfunction "2_2") (pintype "passive"))
      (node (ref "C7") (pin "2") (pinfunction "2_2") (pintype "passive"))
      (node (ref "C8") (pin "2") (pinfunction "2_2") (pintype "passive"))
      (node (ref "C9") (pin "2") (pinfunction "2_2") (pintype "passive"))
      (node (ref "D1") (pin "13") (pinfunction "GND_13") (pintype "power_in"))
      (node (ref "D1") (pin "19") (pinfunction "GND_19") (pintype "power_in"))
      (node (ref "D1") (pin "21") (pinfunction "GND_21") (pintype "power_in"))
      (node (ref "D1") (pin "27") (pinfunction "GND_27") (pintype "power_in"))
      (node (ref "D1") (pin "30") (pinfunction "GND_30") (pintype "power_in"))
      (node (ref "D1") (pin "31") (pinfunction "GND_31") (pintype "power_in"))
      (node (ref "D1") (pin "33") (pinfunction "GND_33") (pintype "power_in"))
      (node (ref "D1") (pin "36") (pinfunction "GND_36") (pintype "power_in"))
      (node (ref "D1") (pin "37") (pinfunction "GND_37") (pintype "power_in"))
      (node (ref "D1") (pin "8") (pinfunction "GND_8") (pintype "power_in"))
      (node (ref "D4") (pin "1") (pinfunction "GND_1") (pintype "passive"))
      (node (ref "D4") (pin "10") (pinfunction "GND_10") (pintype "passive"))
      (node (ref "D4") (pin "12") (pinfunction "GND_12") (pintype "passive"))
      (node (ref "DA1") (pin "2") (pinfunction "GND_2") (pintype "passive"))
      (node (ref "DA2") (pin "3") (pinfunction "EN1_3") (pintype "passive"))
      (node (ref "DA2") (pin "6") (pinfunction "GND_6") (pintype "passive"))
      (node (ref "DA2") (pin "9") (pinfunction "EPAD_9") (pintype "passive"))
      (node (ref "DA3") (pin "5") (pinfunction "NC_5") (pintype "passive"))
      (node (ref "DA3") (pin "8") (pinfunction "GND_8") (pintype "power_in"))
      (node (ref "DA3") (pin "9") (pinfunction "EPAD_9") (pintype "power_in"))
      (node (ref "DA4") (pin "2") (pinfunction "GND_2") (pintype "passive"))
      (node (ref "DD1") (pin "23") (pinfunction "VSS1_23") (pintype "passive"))
      (node (ref "DD1") (pin "35") (pinfunction "Vss2_35") (pintype "passive"))
      (node (ref "DD1") (pin "47") (pinfunction "Vss3_47") (pintype "passive"))
      (node (ref "DD1") (pin "8") (pinfunction "Vssa_8") (pintype "passive"))
      (node (ref "DD2") (pin "12") (pinfunction "GND_12") (pintype "passive"))
      (node (ref "DD2") (pin "13") (pinfunction "GND_13") (pintype "passive"))
      (node (ref "DD2") (pin "16") (pinfunction "GND_16") (pintype "passive"))
      (node (ref "DD2") (pin "5") (pinfunction "GND_5") (pintype "passive"))
      (node (ref "DS1") (pin "4") (pinfunction "GND_4") (pintype "passive"))
      (node (ref "R10") (pin "1") (pinfunction "1_1") (pintype "passive"))
      (node (ref "R11") (pin "2") (pinfunction "2_2") (pintype "passive"))
      (node (ref "R19") (pin "2") (pinfunction "2_2") (pintype "passive"))
      (node (ref "R4") (pin "2") (pinfunction "2_2") (pintype "passive"))
      (node (ref "R5") (pin "2") (pinfunction "2_2") (pintype "passive"))
      (node (ref "R7") (pin "2") (pinfunction "2_2") (pintype "passive"))
      (node (ref "R8") (pin "1") (pinfunction "1_1") (pintype "passive"))
      (node (ref "R9") (pin "2") (pinfunction "2_2") (pintype "passive"))
      (node (ref "TP5") (pin "1") (pintype "passive"))
      (node (ref "VD2") (pin "A") (pinfunction "1_A") (pintype "passive"))
      (node (ref "VD3") (pin "C") (pinfunction "cathode_C") (pintype "passive"))
      (node (ref "VD5") (pin "2") (pinfunction "DC-_2") (pintype "passive"))
      (node (ref "VT1") (pin "2") (pinfunction "S_2") (pintype "passive"))
      (node (ref "WA1") (pin "2") (pinfunction "2_2") (pintype "power_in"))
      (node (ref "X1") (pin "4") (pinfunction "SH1_4") (pintype "passive"))
      (node (ref "X1") (pin "8") (pinfunction "SH2_8") (pintype "passive"))
      (node (ref "ZQ2") (pin "2") (pinfunction "2_2") (pintype "passive"))
    )
    (net (code "37") (name "Net-(C10-P2)") (class "Default")
      (node (ref "C10") (pin "2") (pinfunction "P2_2") (pintype "passive"))
      (node (ref "DA3") (pin "7") (pinfunction "ADJ_7") (pintype "passive"))
      (node (ref "R3") (pin "1") (pinfunction "1_1") (pintype "passive"))
      (node (ref "R4") (pin "1") (pinfunction "1_1") (pintype "passive"))
    )
    (net (code "38") (name "Net-(C13-P2)") (class "Default")
      (node (ref "C13") (pin "2") (pinfunction "P2_2") (pintype "passive"))
      (node (ref "DA2") (pin "4") (pinfunction "FB_4") (pintype "passive"))
      (node (ref "R2") (pin "1") (pinfunction "1_1") (pintype "passive"))
      (node (ref "R5") (pin "1") (pinfunction "1_1") (pintype "passive"))
    )
    (net (code "39") (name "Net-(C22-P1)") (class "Default")
      (node (ref "C22") (pin "1") (pinfunction "P1_1") (pintype "passive"))
      (node (ref "DD1") (pin "3") (pinfunction "PC14/OSC32_IN_3") (pintype "passive"))
      (node (ref "ZQ1") (pin "1") (pinfunction "1_1") (pintype "passive"))
    )
    (net (code "40") (name "Net-(C23-P1)") (class "Default")
      (node (ref "C23") (pin "1") (pinfunction "P1_1") (pintype "passive"))
      (node (ref "DD1") (pin "4") (pinfunction "PC15/OSC32_OUT_4") (pintype "passive"))
      (node (ref "ZQ1") (pin "2") (pinfunction "2_2") (pintype "passive"))
    )
    (net (code "41") (name "Net-(C28-Pad1)") (class "Default")
      (node (ref "C28") (pin "1") (pinfunction "1_1") (pintype "passive"))
      (node (ref "R14") (pin "1") (pinfunction "1_1") (pintype "passive"))
    )
    (net (code "42") (name "Net-(DA2-Boot)") (class "Default")
      (node (ref "C5") (pin "2") (pinfunction "2_2") (pintype "passive"))
      (node (ref "DA2") (pin "1") (pinfunction "Boot_1") (pintype "passive"))
    )
    (net (code "43") (name "Net-(DA2-SW)") (class "Default")
      (node (ref "C5") (pin "1") (pinfunction "1_1") (pintype "passive"))
      (node (ref "DA2") (pin "8") (pinfunction "SW_8") (pintype "passive"))
      (node (ref "L1") (pin "1") (pinfunction "1_1") (pintype "passive"))
      (node (ref "VD2") (pin "C") (pinfunction "2_C") (pintype "passive"))
    )
    (net (code "44") (name "Net-(DD1-PH0-OSC_IN)") (class "Default")
      (node (ref "DD1") (pin "5") (pinfunction "PH0-OSC_IN_5") (pintype "passive"))
      (node (ref "ZQ2") (pin "1") (pinfunction "1_1") (pintype "passive"))
    )
    (net (code "45") (name "Net-(DD1-PH1-OSC_OUT)") (class "Default")
      (node (ref "DD1") (pin "6") (pinfunction "PH1-OSC_OUT_6") (pintype "passive"))
      (node (ref "ZQ2") (pin "3") (pinfunction "3_3") (pintype "passive"))
    )
    (net (code "46") (name "Net-(VD3-anod)") (class "Default")
      (node (ref "R13") (pin "2") (pinfunction "2_2") (pintype "passive"))
      (node (ref "VD3") (pin "A") (pinfunction "anod_A") (pintype "passive"))
    )
    (net (code "47") (name "SIM_GND") (class "Default")
      (node (ref "D3") (pin "1") (pinfunction "Vss_1") (pintype "passive"))
      (node (ref "VT1") (pin "3") (pinfunction "D_3") (pintype "passive"))
      (node (ref "X1") (pin "5") (pinfunction "GND_5") (pintype "passive"))
    )
    (net (code "48") (name "SIM_VDD") (class "Default")
      (node (ref "C14") (pin "2") (pinfunction "P2_2") (pintype "passive"))
      (node (ref "D1") (pin "18") (pinfunction "SIM_VDD_18") (pintype "power_in"))
      (node (ref "D3") (pin "8") (pinfunction "VDD_8") (pintype "passive"))
      (node (ref "R1") (pin "1") (pinfunction "1_1") (pintype "passive"))
      (node (ref "X1") (pin "1") (pinfunction "VCC_1") (pintype "passive"))
    )
    (net (code "49") (name "U_MAIN") (class "Default")
      (node (ref "C6") (pin "1") (pinfunction "1_1") (pintype "passive"))
      (node (ref "C7") (pin "1") (pinfunction "1_1") (pintype "passive"))
      (node (ref "DA2") (pin "5") (pinfunction "EN2_5") (pintype "passive"))
      (node (ref "DA2") (pin "7") (pinfunction "Vin_7") (pintype "passive"))
      (node (ref "R6") (pin "1") (pinfunction "1_1") (pintype "passive"))
      (node (ref "VD5") (pin "1") (pinfunction "DC+_1") (pintype "passive"))
    )
    (net (code "50") (name "unconnected-(D1-ADC-Pad38)") (class "Default")
      (node (ref "D1") (pin "38") (pinfunction "ADC_38") (pintype "input"))
    )
    (net (code "51") (name "unconnected-(D1-BT_ANT-Pad20)") (class "Default")
      (node (ref "D1") (pin "20") (pinfunction "BT_ANT_20") (pintype "bidirectional"))
    )
    (net (code "52") (name "unconnected-(D1-MICN-Pad10)") (class "Default")
      (node (ref "D1") (pin "10") (pinfunction "MICN_10") (pintype "input"))
    )
    (net (code "53") (name "unconnected-(D1-MICP-Pad9)") (class "Default")
      (node (ref "D1") (pin "9") (pinfunction "MICP_9") (pintype "input"))
    )
    (net (code "54") (name "unconnected-(D1-NETLIGHT-Pad41)") (class "Default")
      (node (ref "D1") (pin "41") (pinfunction "NETLIGHT_41") (pintype "output"))
    )
    (net (code "55") (name "unconnected-(D1-RF_SYNC-Pad29)") (class "Default")
      (node (ref "D1") (pin "29") (pinfunction "RF_SYNC_29") (pintype "output"))
    )
    (net (code "56") (name "unconnected-(D1-SIM1_DET-Pad14)") (class "Default")
      (node (ref "D1") (pin "14") (pinfunction "SIM1_DET_14") (pintype "input"))
    )
    (net (code "57") (name "unconnected-(D1-SPKN-Pad12)") (class "Default")
      (node (ref "D1") (pin "12") (pinfunction "SPKN_12") (pintype "output"))
    )
    (net (code "58") (name "unconnected-(D1-SPKP-Pad11)") (class "Default")
      (node (ref "D1") (pin "11") (pinfunction "SPKP_11") (pintype "output"))
    )
    (net (code "59") (name "unconnected-(D1-STATUS-Pad42)") (class "Default")
      (node (ref "D1") (pin "42") (pinfunction "STATUS_42") (pintype "output"))
    )
    (net (code "60") (name "unconnected-(D1-UART1_CTS-Pad4)") (class "Default")
      (node (ref "D1") (pin "4") (pinfunction "UART1_CTS_4") (pintype "output"))
    )
    (net (code "61") (name "unconnected-(D1-UART1_DCD-Pad5)") (class "Default")
      (node (ref "D1") (pin "5") (pinfunction "UART1_DCD_5") (pintype "output"))
    )
    (net (code "62") (name "unconnected-(D1-UART1_DTR-Pad6)") (class "Default")
      (node (ref "D1") (pin "6") (pinfunction "UART1_DTR_6") (pintype "input"))
    )
    (net (code "63") (name "unconnected-(D1-UART1_RI-Pad7)") (class "Default")
      (node (ref "D1") (pin "7") (pinfunction "UART1_RI_7") (pintype "output"))
    )
    (net (code "64") (name "unconnected-(D1-UART1_RTS-Pad3)") (class "Default")
      (node (ref "D1") (pin "3") (pinfunction "UART1_RTS_3") (pintype "input"))
    )
    (net (code "65") (name "unconnected-(D1-UART2_RXD-Pad23)") (class "Default")
      (node (ref "D1") (pin "23") (pinfunction "UART2_RXD_23") (pintype "input"))
    )
    (net (code "66") (name "unconnected-(D1-UART2_TXD-Pad22)") (class "Default")
      (node (ref "D1") (pin "22") (pinfunction "UART2_TXD_22") (pintype "output"))
    )
    (net (code "67") (name "unconnected-(D1-USB_DM-Pad26)") (class "Default")
      (node (ref "D1") (pin "26") (pinfunction "USB_DM_26") (pintype "bidirectional"))
    )
    (net (code "68") (name "unconnected-(D1-USB_DP-Pad25)") (class "Default")
      (node (ref "D1") (pin "25") (pinfunction "USB_DP_25") (pintype "bidirectional"))
    )
    (net (code "69") (name "unconnected-(D1-USB_VBUS-Pad24)") (class "Default")
      (node (ref "D1") (pin "24") (pinfunction "USB_VBUS_24") (pintype "power_in"))
    )
    (net (code "70") (name "unconnected-(D1-VDD_EXT-Pad40)") (class "Default")
      (node (ref "D1") (pin "40") (pinfunction "VDD_EXT_40") (pintype "power_in"))
    )
    (net (code "71") (name "unconnected-(D1-VRTC-Pad28)") (class "Default")
      (node (ref "D1") (pin "28") (pinfunction "VRTC_28") (pintype "power_in"))
    )
    (net (code "72") (name "unconnected-(D3-NA-Pad2)") (class "Default")
      (node (ref "D3") (pin "2") (pinfunction "NA_2") (pintype "passive"))
    )
    (net (code "73") (name "unconnected-(D4-ANT_ON_(Reserved)-Pad13)") (class "Default")
      (node (ref "D4") (pin "13") (pinfunction "ANT_ON_(Reserved)_13") (pintype "output"))
    )
    (net (code "74") (name "unconnected-(D4-EXTINT-Pad5)") (class "Default")
      (node (ref "D4") (pin "5") (pinfunction "EXTINT_5") (pintype "input"))
    )
    (net (code "75") (name "unconnected-(D4-RESET_N-Pad9)") (class "Default")
      (node (ref "D4") (pin "9") (pinfunction "RESET_N_9") (pintype "input"))
    )
    (net (code "76") (name "unconnected-(D4-Reserved-Pad18)") (class "Default")
      (node (ref "D4") (pin "18") (pinfunction "Reserved_18") (pintype "passive"))
    )
    (net (code "77") (name "unconnected-(D4-SCL-Pad17)") (class "Default")
      (node (ref "D4") (pin "17") (pinfunction "SCL_17") (pintype "bidirectional"))
    )
    (net (code "78") (name "unconnected-(D4-SDA-Pad16)") (class "Default")
      (node (ref "D4") (pin "16") (pinfunction "SDA_16") (pintype "bidirectional"))
    )
    (net (code "79") (name "unconnected-(D4-TIMEPULSE-Pad4)") (class "Default")
      (node (ref "D4") (pin "4") (pinfunction "TIMEPULSE_4") (pintype "output"))
    )
    (net (code "80") (name "unconnected-(D4-VCC_RF-Pad14)") (class "Default")
      (node (ref "D4") (pin "14") (pinfunction "VCC_RF_14") (pintype "power_in"))
    )
    (net (code "81") (name "unconnected-(D4-V_ANT_(Reserved)-Pad15)") (class "Default")
      (node (ref "D4") (pin "15") (pinfunction "V_ANT_(Reserved)_15") (pintype "power_in"))
    )
    (net (code "82") (name "unconnected-(DA1-NC{slash}FB-Pad4)") (class "Default")
      (node (ref "DA1") (pin "4") (pinfunction "NC/FB_4") (pintype "passive"))
    )
    (net (code "83") (name "unconnected-(DA2-PGOOD-Pad2)") (class "Default")
      (node (ref "DA2") (pin "2") (pinfunction "PGOOD_2") (pintype "passive"))
    )
    (net (code "84") (name "unconnected-(DA3-PGOOD-Pad1)") (class "Default")
      (node (ref "DA3") (pin "1") (pinfunction "PGOOD_1") (pintype "output+no_connect"))
    )
    (net (code "85") (name "unconnected-(DA4-NC{slash}FB-Pad4)") (class "Default")
      (node (ref "DA4") (pin "4") (pinfunction "NC/FB_4") (pintype "passive"))
    )
    (net (code "86") (name "unconnected-(DD1-PA1-Pad11)") (class "Default")
      (node (ref "DD1") (pin "11") (pinfunction "PA1_11") (pintype "passive"))
    )
    (net (code "87") (name "unconnected-(DD1-PA8-Pad29)") (class "Default")
      (node (ref "DD1") (pin "29") (pinfunction "PA8_29") (pintype "passive"))
    )
    (net (code "88") (name "unconnected-(DD1-PA12-Pad33)") (class "Default")
      (node (ref "DD1") (pin "33") (pinfunction "PA12_33") (pintype "passive"))
    )
    (net (code "89") (name "unconnected-(DD1-PB3{slash}JTDO-Pad39)") (class "Default")
      (node (ref "DD1") (pin "39") (pinfunction "PB3/JTDO_39") (pintype "passive"))
    )
    (net (code "90") (name "unconnected-(DD1-PB4{slash}nJTRST-Pad40)") (class "Default")
      (node (ref "DD1") (pin "40") (pinfunction "PB4/nJTRST_40") (pintype "passive"))
    )
    (net (code "91") (name "unconnected-(DD1-PB5-Pad41)") (class "Default")
      (node (ref "DD1") (pin "41") (pinfunction "PB5_41") (pintype "passive"))
    )
    (net (code "92") (name "unconnected-(DD1-PB6-Pad42)") (class "Default")
      (node (ref "DD1") (pin "42") (pinfunction "PB6_42") (pintype "passive"))
    )
    (net (code "93") (name "unconnected-(DD1-PB7-Pad43)") (class "Default")
      (node (ref "DD1") (pin "43") (pinfunction "PB7_43") (pintype "passive"))
    )
    (net (code "94") (name "unconnected-(DD1-PB8-Pad45)") (class "Default")
      (node (ref "DD1") (pin "45") (pinfunction "PB8_45") (pintype "passive"))
    )
    (net (code "95") (name "unconnected-(DD1-PB13{slash}SCK2-Pad26)") (class "Default")
      (node (ref "DD1") (pin "26") (pinfunction "PB13/SCK2_26") (pintype "passive"))
    )
    (net (code "96") (name "unconnected-(DD1-PB14{slash}MISO2-Pad27)") (class "Default")
      (node (ref "DD1") (pin "27") (pinfunction "PB14/MISO2_27") (pintype "passive"))
    )
    (net (code "97") (name "unconnected-(DD1-PC13-WKUP2-Pad2)") (class "Default")
      (node (ref "DD1") (pin "2") (pinfunction "PC13-WKUP2_2") (pintype "passive"))
    )
    (net (code "98") (name "unconnected-(DD1-TPAD-Pad49)") (class "Default")
      (node (ref "DD1") (pin "49") (pinfunction "TPAD_49") (pintype "passive"))
    )
    (net (code "99") (name "unconnected-(DD2-INT2-Pad9)") (class "Default")
      (node (ref "DD2") (pin "9") (pinfunction "INT2_9") (pintype "passive"))
    )
    (net (code "100") (name "unconnected-(DD2-NC-Pad2)") (class "Default")
      (node (ref "DD2") (pin "2") (pinfunction "NC_2") (pintype "passive"))
    )
    (net (code "101") (name "unconnected-(DD2-NC-Pad3)") (class "Default")
      (node (ref "DD2") (pin "3") (pinfunction "NC_3") (pintype "passive"))
    )
    (net (code "102") (name "unconnected-(DD2-RESERVED-Pad10)") (class "Default")
      (node (ref "DD2") (pin "10") (pinfunction "RESERVED_10") (pintype "passive"))
    )
    (net (code "103") (name "unconnected-(DD2-RESERVED-Pad15)") (class "Default")
      (node (ref "DD2") (pin "15") (pinfunction "RESERVED_15") (pintype "passive"))
    )
    (net (code "104") (name "unconnected-(X1-VPP-Pad6)") (class "Default")
      (node (ref "X1") (pin "6") (pinfunction "VPP_6") (pintype "passive"))
    )
  )
)
